# tile.net
KiCad netlist of a schematic drawn in EAGLE
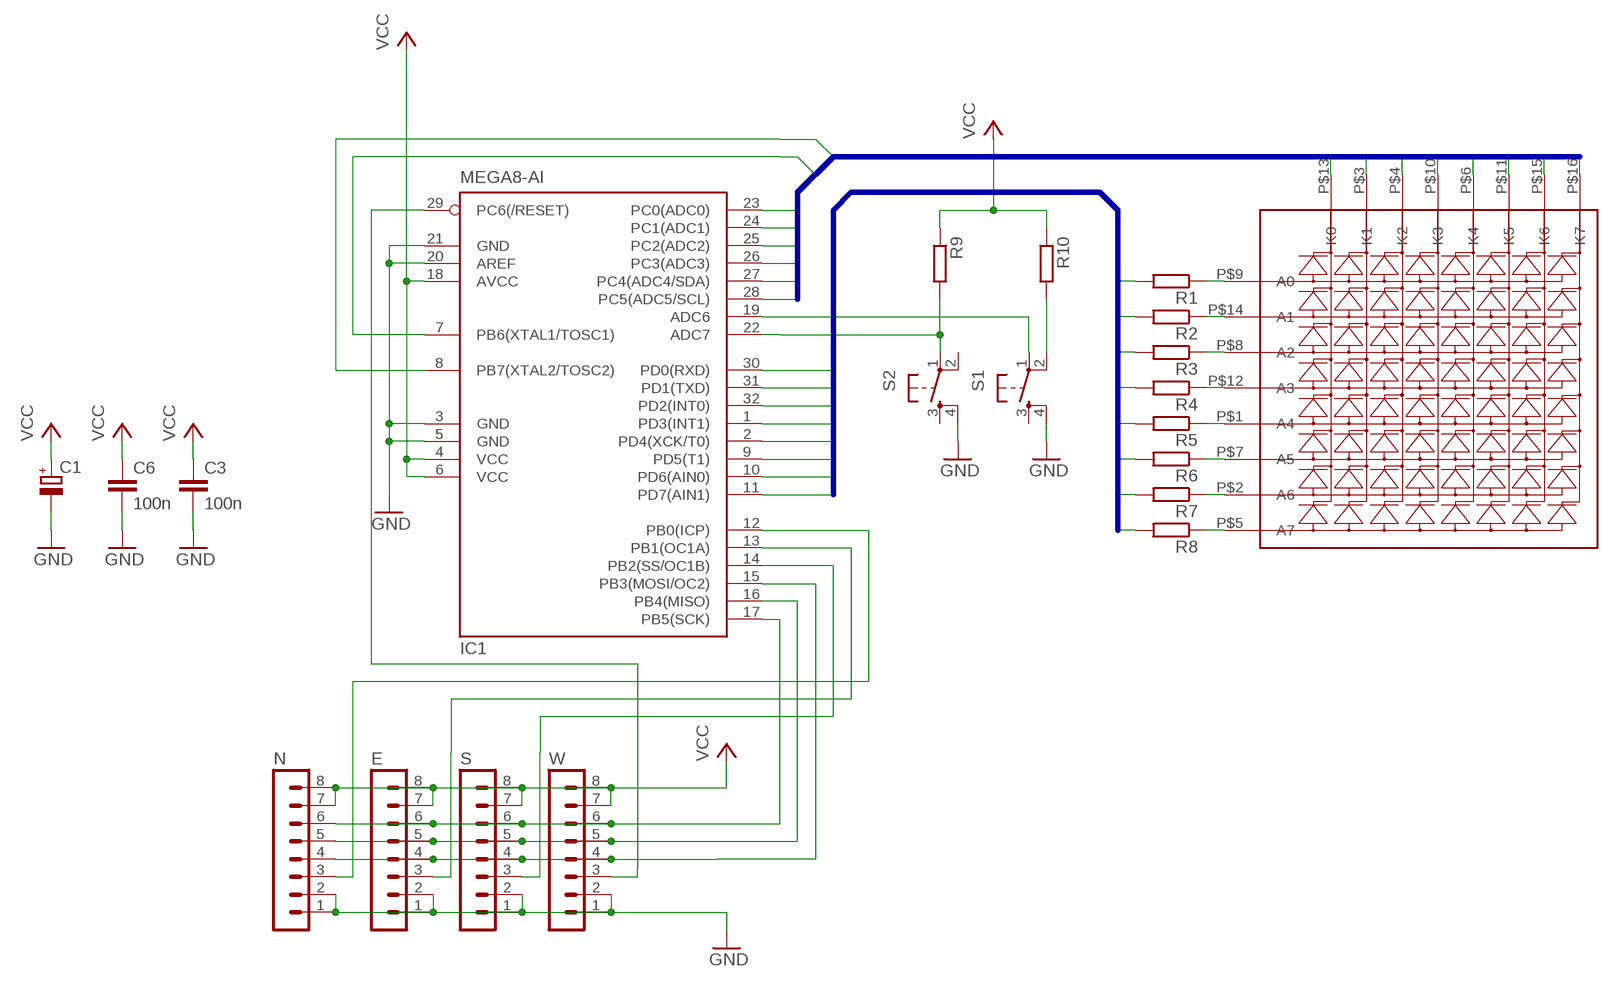
[diagram p0: schematic, sheet 1]

(export (version "E")
  (design (tool "Eeschema 10.0.6"))
  (components
    (comp (ref "C1")
      (value "CPOL-EUB")
      (footprint "eagle-import:PANASONIC_B")
      (libsource (lib "eagle-import") (part "CPOL-EUB"))
    )
    (comp (ref "C3")
      (value "100n")
      (footprint "eagle-import:C0805")
      (libsource (lib "eagle-import") (part "C-EUC0805"))
    )
    (comp (ref "C6")
      (value "100n")
      (footprint "eagle-import:C0805")
      (libsource (lib "eagle-import") (part "C-EUC0805"))
    )
    (comp (ref "E")
      (value "MA08-1")
      (footprint "eagle-import:MA08-1")
      (libsource (lib "eagle-import") (part "MA08-1"))
    )
    (comp (ref "IC1")
      (value "MEGA8-AI")
      (footprint "eagle-import:TQFP32-08")
      (libsource (lib "eagle-import") (part "MEGA8-AI"))
    )
    (comp (ref "N")
      (value "MA08-1")
      (footprint "eagle-import:MA08-1")
      (libsource (lib "eagle-import") (part "MA08-1"))
    )
    (comp (ref "R1")
      (value "R-EU_M0805")
      (footprint "eagle-import:M0805")
      (libsource (lib "eagle-import") (part "R-EU_M0805"))
    )
    (comp (ref "R2")
      (value "R-EU_M0805")
      (footprint "eagle-import:M0805")
      (libsource (lib "eagle-import") (part "R-EU_M0805"))
    )
    (comp (ref "R3")
      (value "R-EU_M0805")
      (footprint "eagle-import:M0805")
      (libsource (lib "eagle-import") (part "R-EU_M0805"))
    )
    (comp (ref "R4")
      (value "R-EU_M0805")
      (footprint "eagle-import:M0805")
      (libsource (lib "eagle-import") (part "R-EU_M0805"))
    )
    (comp (ref "R5")
      (value "R-EU_M0805")
      (footprint "eagle-import:M0805")
      (libsource (lib "eagle-import") (part "R-EU_M0805"))
    )
    (comp (ref "R6")
      (value "R-EU_M0805")
      (footprint "eagle-import:M0805")
      (libsource (lib "eagle-import") (part "R-EU_M0805"))
    )
    (comp (ref "R7")
      (value "R-EU_M0805")
      (footprint "eagle-import:M0805")
      (libsource (lib "eagle-import") (part "R-EU_M0805"))
    )
    (comp (ref "R8")
      (value "R-EU_M0805")
      (footprint "eagle-import:M0805")
      (libsource (lib "eagle-import") (part "R-EU_M0805"))
    )
    (comp (ref "R9")
      (value "R-EU_M0805")
      (footprint "eagle-import:M0805")
      (libsource (lib "eagle-import") (part "R-EU_M0805"))
    )
    (comp (ref "R10")
      (value "R-EU_M0805")
      (footprint "eagle-import:M0805")
      (libsource (lib "eagle-import") (part "R-EU_M0805"))
    )
    (comp (ref "S")
      (value "MA08-1")
      (footprint "eagle-import:MA08-1")
      (libsource (lib "eagle-import") (part "MA08-1"))
    )
    (comp (ref "S1")
      (value "TAC_SWITCHSMD")
      (footprint "eagle-import:TACTILE_SWITCH_SMD")
      (fields (field (name "PROD_ID") "SWCH-08247"))
      (libsource (lib "eagle-import") (part "TAC_SWITCHSMD"))
    )
    (comp (ref "S2")
      (value "TAC_SWITCHSMD")
      (footprint "eagle-import:TACTILE_SWITCH_SMD")
      (libsource (lib "eagle-import") (part "TAC_SWITCHSMD"))
    )
    (comp (ref "U$1")
      (value "LED-MATRIX")
      (footprint "eagle-import:LED-MATRIX")
      (libsource (lib "eagle-import") (part "LED-MATRIX"))
    )
    (comp (ref "W")
      (value "MA08-1")
      (footprint "eagle-import:MA08-1")
      (libsource (lib "eagle-import") (part "MA08-1"))
    )
  )
  (nets
    (net (code "1") (name "/A0") (class "Default")
      (node (ref "IC1") (pin "30") (pinfunction "PD0(RXD)_30") (pintype "bidirectional"))
      (node (ref "R1") (pin "2") (pinfunction "2_2") (pintype "passive"))
    )
    (net (code "2") (name "/A1") (class "Default")
      (node (ref "IC1") (pin "31") (pinfunction "PD1(TXD)_31") (pintype "bidirectional"))
      (node (ref "R2") (pin "2") (pinfunction "2_2") (pintype "passive"))
    )
    (net (code "3") (name "/A2") (class "Default")
      (node (ref "IC1") (pin "32") (pinfunction "PD2(INT0)_32") (pintype "bidirectional"))
      (node (ref "R3") (pin "2") (pinfunction "2_2") (pintype "passive"))
    )
    (net (code "4") (name "/A3") (class "Default")
      (node (ref "IC1") (pin "1") (pinfunction "PD3(INT1)_1") (pintype "bidirectional"))
      (node (ref "R4") (pin "2") (pinfunction "2_2") (pintype "passive"))
    )
    (net (code "5") (name "/A4") (class "Default")
      (node (ref "IC1") (pin "2") (pinfunction "PD4(XCK/T0)_2") (pintype "bidirectional"))
      (node (ref "R5") (pin "2") (pinfunction "2_2") (pintype "passive"))
    )
    (net (code "6") (name "/A5") (class "Default")
      (node (ref "IC1") (pin "9") (pinfunction "PD5(T1)_9") (pintype "bidirectional"))
      (node (ref "R6") (pin "2") (pinfunction "2_2") (pintype "passive"))
    )
    (net (code "7") (name "/A6") (class "Default")
      (node (ref "IC1") (pin "10") (pinfunction "PD6(AIN0)_10") (pintype "bidirectional"))
      (node (ref "R7") (pin "2") (pinfunction "2_2") (pintype "passive"))
    )
    (net (code "8") (name "/A7") (class "Default")
      (node (ref "IC1") (pin "11") (pinfunction "PD7(AIN1)_11") (pintype "bidirectional"))
      (node (ref "R8") (pin "2") (pinfunction "2_2") (pintype "passive"))
    )
    (net (code "9") (name "/K0") (class "Default")
      (node (ref "IC1") (pin "23") (pinfunction "PC0(ADC0)_23") (pintype "bidirectional"))
      (node (ref "U$1") (pin "P$13") (pinfunction "K0_P$13") (pintype "bidirectional"))
    )
    (net (code "10") (name "/K1") (class "Default")
      (node (ref "IC1") (pin "24") (pinfunction "PC1(ADC1)_24") (pintype "bidirectional"))
      (node (ref "U$1") (pin "P$3") (pinfunction "K1_P$3") (pintype "bidirectional"))
    )
    (net (code "11") (name "/K2") (class "Default")
      (node (ref "IC1") (pin "25") (pinfunction "PC2(ADC2)_25") (pintype "bidirectional"))
      (node (ref "U$1") (pin "P$4") (pinfunction "K2_P$4") (pintype "bidirectional"))
    )
    (net (code "12") (name "/K3") (class "Default")
      (node (ref "IC1") (pin "26") (pinfunction "PC3(ADC3)_26") (pintype "bidirectional"))
      (node (ref "U$1") (pin "P$10") (pinfunction "K3_P$10") (pintype "bidirectional"))
    )
    (net (code "13") (name "/K4") (class "Default")
      (node (ref "IC1") (pin "27") (pinfunction "PC4(ADC4/SDA)_27") (pintype "bidirectional"))
      (node (ref "U$1") (pin "P$6") (pinfunction "K4_P$6") (pintype "bidirectional"))
    )
    (net (code "14") (name "/K5") (class "Default")
      (node (ref "IC1") (pin "28") (pinfunction "PC5(ADC5/SCL)_28") (pintype "bidirectional"))
      (node (ref "U$1") (pin "P$11") (pinfunction "K5_P$11") (pintype "bidirectional"))
    )
    (net (code "15") (name "/K6") (class "Default")
      (node (ref "IC1") (pin "7") (pinfunction "PB6(XTAL1/TOSC1)_7") (pintype "bidirectional"))
      (node (ref "U$1") (pin "P$15") (pinfunction "K6_P$15") (pintype "bidirectional"))
    )
    (net (code "16") (name "/K7") (class "Default")
      (node (ref "IC1") (pin "8") (pinfunction "PB7(XTAL2/TOSC2)_8") (pintype "bidirectional"))
      (node (ref "U$1") (pin "P$16") (pinfunction "K7_P$16") (pintype "bidirectional"))
    )
    (net (code "17") (name "GND") (class "Default")
      (node (ref "C1") (pin "-") (pinfunction "-_-") (pintype "passive"))
      (node (ref "C3") (pin "2") (pinfunction "2_2") (pintype "passive"))
      (node (ref "C6") (pin "2") (pinfunction "2_2") (pintype "passive"))
      (node (ref "E") (pin "1") (pinfunction "1_1") (pintype "passive"))
      (node (ref "E") (pin "2") (pinfunction "2_2") (pintype "passive"))
      (node (ref "IC1") (pin "20") (pinfunction "AREF_20") (pintype "passive"))
      (node (ref "IC1") (pin "21") (pinfunction "GND_21") (pintype "power_in"))
      (node (ref "IC1") (pin "3") (pinfunction "GND_3") (pintype "power_in"))
      (node (ref "IC1") (pin "5") (pinfunction "GND_5") (pintype "power_in"))
      (node (ref "N") (pin "1") (pinfunction "1_1") (pintype "passive"))
      (node (ref "N") (pin "2") (pinfunction "2_2") (pintype "passive"))
      (node (ref "S") (pin "1") (pinfunction "1_1") (pintype "passive"))
      (node (ref "S") (pin "2") (pinfunction "2_2") (pintype "passive"))
      (node (ref "S1") (pin "4") (pinfunction "4_4") (pintype "passive"))
      (node (ref "S2") (pin "4") (pinfunction "4_4") (pintype "passive"))
      (node (ref "W") (pin "1") (pinfunction "1_1") (pintype "passive"))
      (node (ref "W") (pin "2") (pinfunction "2_2") (pintype "passive"))
    )
    (net (code "18") (name "Net-(IC1-ADC6)") (class "Default")
      (node (ref "IC1") (pin "19") (pinfunction "ADC6_19") (pintype "bidirectional"))
      (node (ref "S1") (pin "1") (pinfunction "1_1") (pintype "passive"))
    )
    (net (code "19") (name "Net-(IC1-ADC7)") (class "Default")
      (node (ref "IC1") (pin "22") (pinfunction "ADC7_22") (pintype "bidirectional"))
      (node (ref "R9") (pin "2") (pinfunction "2_2") (pintype "passive"))
      (node (ref "S2") (pin "1") (pinfunction "1_1") (pintype "passive"))
    )
    (net (code "20") (name "Net-(IC1-PB0(ICP))") (class "Default")
      (node (ref "IC1") (pin "12") (pinfunction "PB0(ICP)_12") (pintype "bidirectional"))
      (node (ref "N") (pin "3") (pinfunction "3_3") (pintype "passive"))
    )
    (net (code "21") (name "Net-(IC1-PB1(OC1A))") (class "Default")
      (node (ref "E") (pin "3") (pinfunction "3_3") (pintype "passive"))
      (node (ref "IC1") (pin "13") (pinfunction "PB1(OC1A)_13") (pintype "bidirectional"))
    )
    (net (code "22") (name "Net-(IC1-PB2(SS{slash}OC1B))") (class "Default")
      (node (ref "IC1") (pin "14") (pinfunction "PB2(SS/OC1B)_14") (pintype "bidirectional"))
      (node (ref "S") (pin "3") (pinfunction "3_3") (pintype "passive"))
    )
    (net (code "23") (name "Net-(IC1-PB3(MOSI{slash}OC2))") (class "Default")
      (node (ref "E") (pin "4") (pinfunction "4_4") (pintype "passive"))
      (node (ref "IC1") (pin "15") (pinfunction "PB3(MOSI/OC2)_15") (pintype "bidirectional"))
      (node (ref "N") (pin "4") (pinfunction "4_4") (pintype "passive"))
      (node (ref "S") (pin "4") (pinfunction "4_4") (pintype "passive"))
      (node (ref "W") (pin "4") (pinfunction "4_4") (pintype "passive"))
    )
    (net (code "24") (name "Net-(IC1-PB4(MISO))") (class "Default")
      (node (ref "E") (pin "5") (pinfunction "5_5") (pintype "passive"))
      (node (ref "IC1") (pin "16") (pinfunction "PB4(MISO)_16") (pintype "bidirectional"))
      (node (ref "N") (pin "5") (pinfunction "5_5") (pintype "passive"))
      (node (ref "S") (pin "5") (pinfunction "5_5") (pintype "passive"))
      (node (ref "W") (pin "5") (pinfunction "5_5") (pintype "passive"))
    )
    (net (code "25") (name "Net-(IC1-PB5(SCK))") (class "Default")
      (node (ref "E") (pin "6") (pinfunction "6_6") (pintype "passive"))
      (node (ref "IC1") (pin "17") (pinfunction "PB5(SCK)_17") (pintype "bidirectional"))
      (node (ref "N") (pin "6") (pinfunction "6_6") (pintype "passive"))
      (node (ref "S") (pin "6") (pinfunction "6_6") (pintype "passive"))
      (node (ref "W") (pin "6") (pinfunction "6_6") (pintype "passive"))
    )
    (net (code "26") (name "Net-(IC1-PC6({slash}RESET))") (class "Default")
      (node (ref "IC1") (pin "29") (pinfunction "PC6(/RESET)_29") (pintype "bidirectional"))
      (node (ref "W") (pin "3") (pinfunction "3_3") (pintype "passive"))
    )
    (net (code "27") (name "Net-(R10-Pad2)") (class "Default")
      (node (ref "R10") (pin "2") (pinfunction "2_2") (pintype "passive"))
      (node (ref "S1") (pin "2") (pinfunction "2_2") (pintype "passive"))
    )
    (net (code "28") (name "Net-(U$1-A0)") (class "Default")
      (node (ref "R1") (pin "1") (pinfunction "1_1") (pintype "passive"))
      (node (ref "U$1") (pin "P$9") (pinfunction "A0_P$9") (pintype "bidirectional"))
    )
    (net (code "29") (name "Net-(U$1-A1)") (class "Default")
      (node (ref "R2") (pin "1") (pinfunction "1_1") (pintype "passive"))
      (node (ref "U$1") (pin "P$14") (pinfunction "A1_P$14") (pintype "bidirectional"))
    )
    (net (code "30") (name "Net-(U$1-A2)") (class "Default")
      (node (ref "R3") (pin "1") (pinfunction "1_1") (pintype "passive"))
      (node (ref "U$1") (pin "P$8") (pinfunction "A2_P$8") (pintype "bidirectional"))
    )
    (net (code "31") (name "Net-(U$1-A3)") (class "Default")
      (node (ref "R4") (pin "1") (pinfunction "1_1") (pintype "passive"))
      (node (ref "U$1") (pin "P$12") (pinfunction "A3_P$12") (pintype "bidirectional"))
    )
    (net (code "32") (name "Net-(U$1-A4)") (class "Default")
      (node (ref "R5") (pin "1") (pinfunction "1_1") (pintype "passive"))
      (node (ref "U$1") (pin "P$1") (pinfunction "A4_P$1") (pintype "bidirectional"))
    )
    (net (code "33") (name "Net-(U$1-A5)") (class "Default")
      (node (ref "R6") (pin "1") (pinfunction "1_1") (pintype "passive"))
      (node (ref "U$1") (pin "P$7") (pinfunction "A5_P$7") (pintype "bidirectional"))
    )
    (net (code "34") (name "Net-(U$1-A6)") (class "Default")
      (node (ref "R7") (pin "1") (pinfunction "1_1") (pintype "passive"))
      (node (ref "U$1") (pin "P$2") (pinfunction "A6_P$2") (pintype "bidirectional"))
    )
    (net (code "35") (name "Net-(U$1-A7)") (class "Default")
      (node (ref "R8") (pin "1") (pinfunction "1_1") (pintype "passive"))
      (node (ref "U$1") (pin "P$5") (pinfunction "A7_P$5") (pintype "bidirectional"))
    )
    (net (code "36") (name "VCC") (class "Default")
      (node (ref "C1") (pin "+") (pinfunction "+_+") (pintype "passive"))
      (node (ref "C3") (pin "1") (pinfunction "1_1") (pintype "passive"))
      (node (ref "C6") (pin "1") (pinfunction "1_1") (pintype "passive"))
      (node (ref "E") (pin "7") (pinfunction "7_7") (pintype "passive"))
      (node (ref "E") (pin "8") (pinfunction "8_8") (pintype "passive"))
      (node (ref "IC1") (pin "18") (pinfunction "AVCC_18") (pintype "power_in"))
      (node (ref "IC1") (pin "4") (pinfunction "VCC_4") (pintype "power_in"))
      (node (ref "IC1") (pin "6") (pinfunction "VCC_6") (pintype "power_in"))
      (node (ref "N") (pin "7") (pinfunction "7_7") (pintype "passive"))
      (node (ref "N") (pin "8") (pinfunction "8_8") (pintype "passive"))
      (node (ref "R10") (pin "1") (pinfunction "1_1") (pintype "passive"))
      (node (ref "R9") (pin "1") (pinfunction "1_1") (pintype "passive"))
      (node (ref "S") (pin "7") (pinfunction "7_7") (pintype "passive"))
      (node (ref "S") (pin "8") (pinfunction "8_8") (pintype "passive"))
      (node (ref "W") (pin "7") (pinfunction "7_7") (pintype "passive"))
      (node (ref "W") (pin "8") (pinfunction "8_8") (pintype "passive"))
    )
    (net (code "37") (name "unconnected-(S1-Pad3)") (class "Default")
      (node (ref "S1") (pin "3") (pinfunction "3_3") (pintype "passive"))
    )
    (net (code "38") (name "unconnected-(S2-Pad2)") (class "Default")
      (node (ref "S2") (pin "2") (pinfunction "2_2") (pintype "passive"))
    )
    (net (code "39") (name "unconnected-(S2-Pad3)") (class "Default")
      (node (ref "S2") (pin "3") (pinfunction "3_3") (pintype "passive"))
    )
  )
)
